# 06_TemperatureSense.net
KiCad netlist of a schematic drawn in Altium Designer
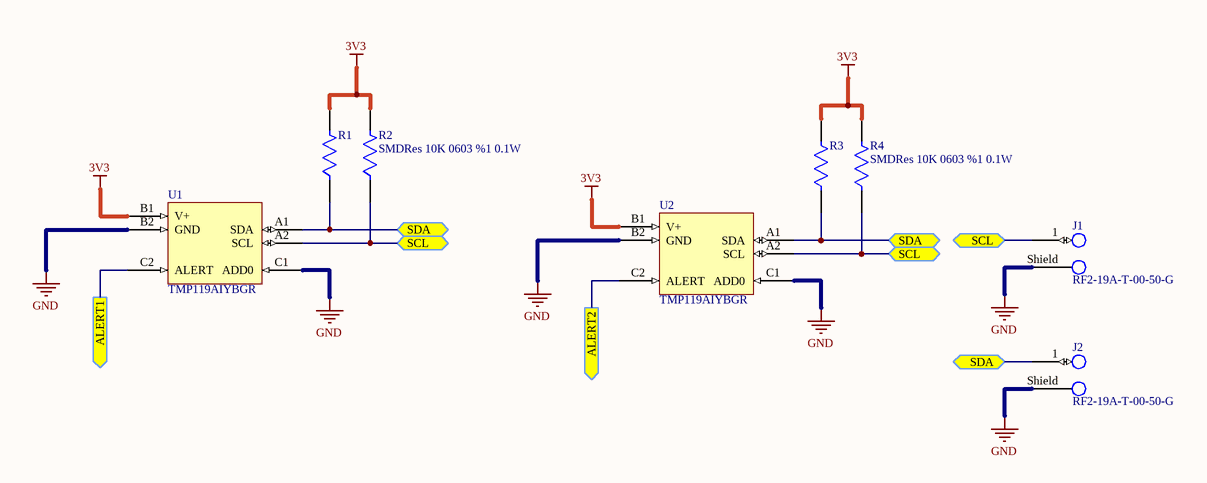
[diagram p0: [06]TemperatureSense.SchDoc]

(export (version "E")
  (design (tool "Eeschema 10.0.6"))
  (components
    (comp (ref "J1")
      (value "RF2-19A-T-00-50-G")
      (footprint "RF2-19A-T-00-50-G")
      (description "Rf Sma Connector")
      (libsource (lib "AGH Power Electronics Lab") (part "RF2-19A-T-00-50-G"))
    )
    (comp (ref "J2")
      (value "RF2-19A-T-00-50-G")
      (footprint "RF2-19A-T-00-50-G")
      (description "Rf Sma Connector")
      (libsource (lib "AGH Power Electronics Lab") (part "RF2-19A-T-00-50-G"))
    )
    (comp (ref "R1")
      (value "SMDRes 10K 0603 %1 0.1W")
      (footprint "RESC1508X06N")
      (description "Res Thick Film 0603 10K Ohm 1% 0.1W(1/10W) ±100ppm/C Pad SMD T/R Automotive AEC-Q200")
      (fields (field (name "POWER") "0.1W") (field (name "DIGI-KEY PART NUMBER") "RMCF0603FT10K0CT-ND"))
      (libsource (lib "AGH Power Electronics Lab") (part "2.2 Ohm"))
    )
    (comp (ref "R2")
      (value "SMDRes 10K 0603 %1 0.1W")
      (footprint "RESC1508X06N")
      (description "Res Thick Film 0603 10K Ohm 1% 0.1W(1/10W) ±100ppm/C Pad SMD T/R Automotive AEC-Q200")
      (fields (field (name "POWER") "0.1W") (field (name "DIGI-KEY PART NUMBER") "RMCF0603FT10K0CT-ND"))
      (libsource (lib "AGH Power Electronics Lab") (part "2.2 Ohm"))
    )
    (comp (ref "R3")
      (value "SMDRes 10K 0603 %1 0.1W")
      (footprint "RESC1508X06N")
      (description "Res Thick Film 0603 10K Ohm 1% 0.1W(1/10W) ±100ppm/C Pad SMD T/R Automotive AEC-Q200")
      (fields (field (name "POWER") "0.1W") (field (name "DIGI-KEY PART NUMBER") "RMCF0603FT10K0CT-ND"))
      (libsource (lib "AGH Power Electronics Lab") (part "2.2 Ohm"))
    )
    (comp (ref "R4")
      (value "SMDRes 10K 0603 %1 0.1W")
      (footprint "RESC1508X06N")
      (description "Res Thick Film 0603 10K Ohm 1% 0.1W(1/10W) ±100ppm/C Pad SMD T/R Automotive AEC-Q200")
      (fields (field (name "POWER") "0.1W") (field (name "DIGI-KEY PART NUMBER") "RMCF0603FT10K0CT-ND"))
      (libsource (lib "AGH Power Electronics Lab") (part "2.2 Ohm"))
    )
    (comp (ref "U1")
      (value "TMP119AIYBGR")
      (footprint "BGA6C40P2X3_95X149X52")
      (description "Temperature Sensor")
      (libsource (lib "AGH Power Electronics Lab") (part "TMP119AIYBGR"))
    )
    (comp (ref "U2")
      (value "TMP119AIYBGR")
      (footprint "BGA6C40P2X3_95X149X52")
      (description "Temperature Sensor")
      (libsource (lib "AGH Power Electronics Lab") (part "TMP119AIYBGR"))
    )
  )
  (nets
    (net (code "1") (name "/ALERT1") (class "Default")
      (node (ref "U1") (pin "C2") (pinfunction "ALERT_C2") (pintype "input"))
    )
    (net (code "2") (name "/ALERT2") (class "Default")
      (node (ref "U2") (pin "C2") (pinfunction "ALERT_C2") (pintype "input"))
    )
    (net (code "3") (name "/SCL") (class "Default")
      (node (ref "J1") (pin "1") (pinfunction "1_1") (pintype "bidirectional"))
      (node (ref "R2") (pin "1") (pinfunction "1_1") (pintype "passive"))
      (node (ref "R4") (pin "1") (pinfunction "1_1") (pintype "passive"))
      (node (ref "U1") (pin "A2") (pinfunction "SCL_A2") (pintype "bidirectional"))
      (node (ref "U2") (pin "A2") (pinfunction "SCL_A2") (pintype "bidirectional"))
    )
    (net (code "4") (name "/SDA") (class "Default")
      (node (ref "J2") (pin "1") (pinfunction "1_1") (pintype "bidirectional"))
      (node (ref "R1") (pin "1") (pinfunction "1_1") (pintype "passive"))
      (node (ref "R3") (pin "1") (pinfunction "1_1") (pintype "passive"))
      (node (ref "U1") (pin "A1") (pinfunction "SDA_A1") (pintype "bidirectional"))
      (node (ref "U2") (pin "A1") (pinfunction "SDA_A1") (pintype "bidirectional"))
    )
    (net (code "5") (name "3V3") (class "Default")
      (node (ref "R1") (pin "2") (pinfunction "2_2") (pintype "passive"))
      (node (ref "R2") (pin "2") (pinfunction "2_2") (pintype "passive"))
      (node (ref "R3") (pin "2") (pinfunction "2_2") (pintype "passive"))
      (node (ref "R4") (pin "2") (pinfunction "2_2") (pintype "passive"))
      (node (ref "U1") (pin "B1") (pinfunction "V+_B1") (pintype "input"))
      (node (ref "U2") (pin "B1") (pinfunction "V+_B1") (pintype "input"))
    )
    (net (code "6") (name "GND") (class "Default")
      (node (ref "J1") (pin "Shield") (pinfunction "Shield_Shield") (pintype "power_in"))
      (node (ref "J2") (pin "Shield") (pinfunction "Shield_Shield") (pintype "power_in"))
      (node (ref "U1") (pin "B2") (pinfunction "GND_B2") (pintype "input"))
      (node (ref "U1") (pin "C1") (pinfunction "ADD0_C1") (pintype "input"))
      (node (ref "U2") (pin "B2") (pinfunction "GND_B2") (pintype "input"))
      (node (ref "U2") (pin "C1") (pinfunction "ADD0_C1") (pintype "input"))
    )
  )
)
